# XBee-Explorer.net
KiCad netlist of a schematic drawn in EAGLE
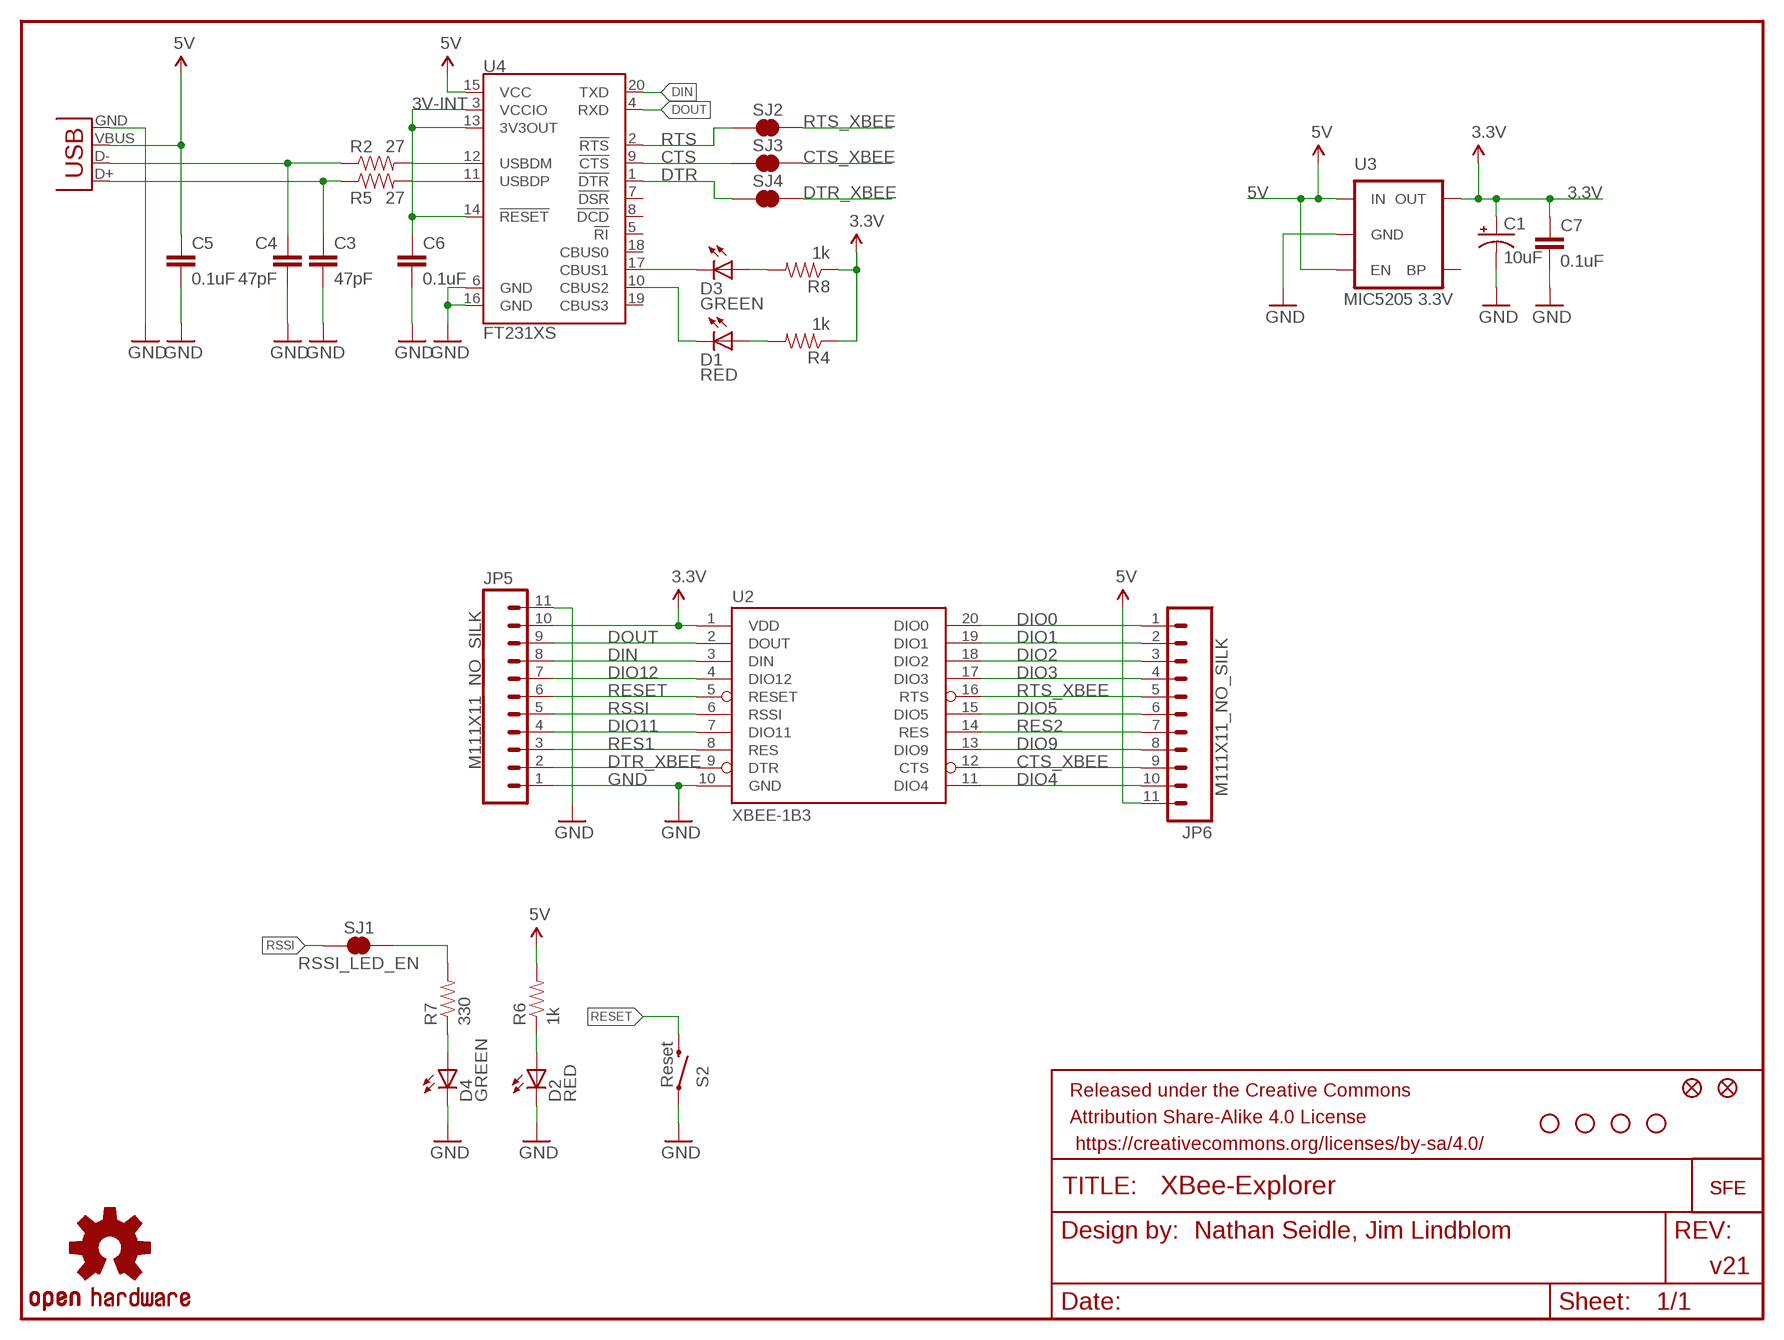
[diagram p0: schematic, sheet 1]

(export (version "E")
  (design (tool "Eeschema 10.0.6"))
  (components
    (comp (ref "C1")
      (value "10uF")
      (footprint "eagle-import:EIA3216")
      (libsource (lib "eagle-import") (part "CAP_POL1206"))
    )
    (comp (ref "C3")
      (value "47pF")
      (footprint "eagle-import:0603-CAP")
      (libsource (lib "eagle-import") (part "CAP0603-CAP"))
    )
    (comp (ref "C4")
      (value "47pF")
      (footprint "eagle-import:0603-CAP")
      (libsource (lib "eagle-import") (part "CAP0603-CAP"))
    )
    (comp (ref "C5")
      (value "0.1uF")
      (footprint "eagle-import:0603-CAP")
      (libsource (lib "eagle-import") (part "CAP0603-CAP"))
    )
    (comp (ref "C6")
      (value "0.1uF")
      (footprint "eagle-import:0603-CAP")
      (libsource (lib "eagle-import") (part "CAP0603-CAP"))
    )
    (comp (ref "C7")
      (value "0.1uF")
      (footprint "eagle-import:0603-CAP")
      (libsource (lib "eagle-import") (part "CAP0603-CAP"))
    )
    (comp (ref "D1")
      (value "RED")
      (footprint "eagle-import:LED-0603")
      (libsource (lib "eagle-import") (part "LED-RED0603"))
    )
    (comp (ref "D2")
      (value "RED")
      (footprint "eagle-import:LED-0603")
      (libsource (lib "eagle-import") (part "LED-RED0603"))
    )
    (comp (ref "D3")
      (value "GREEN")
      (footprint "eagle-import:LED-0603")
      (libsource (lib "eagle-import") (part "LED-GREEN0603"))
    )
    (comp (ref "D4")
      (value "GREEN")
      (footprint "eagle-import:LED-0603")
      (libsource (lib "eagle-import") (part "LED-GREEN0603"))
    )
    (comp (ref "FRAME1")
      (value "FRAME-LETTER")
      (footprint "eagle-import:CREATIVE_COMMONS")
      (libsource (lib "eagle-import") (part "FRAME-LETTER"))
    )
    (comp (ref "JP1")
      (value "FIDUCIAL1X2")
      (footprint "eagle-import:FIDUCIAL-1X2")
      (libsource (lib "eagle-import") (part "FIDUCIAL1X2"))
    )
    (comp (ref "JP4")
      (value "FIDUCIAL1X2")
      (footprint "eagle-import:FIDUCIAL-1X2")
      (libsource (lib "eagle-import") (part "FIDUCIAL1X2"))
    )
    (comp (ref "JP5")
      (value "M111X11_NO_SILK")
      (footprint "eagle-import:1X11_NO_SILK")
      (libsource (lib "eagle-import") (part "M111X11_NO_SILK"))
    )
    (comp (ref "JP6")
      (value "M111X11_NO_SILK")
      (footprint "eagle-import:1X11_NO_SILK")
      (libsource (lib "eagle-import") (part "M111X11_NO_SILK"))
    )
    (comp (ref "LOGO1")
      (value "OSHW-LOGOS")
      (footprint "eagle-import:OSHW-LOGO-S")
      (libsource (lib "eagle-import") (part "OSHW-LOGOS"))
    )
    (comp (ref "R2")
      (value "27")
      (footprint "eagle-import:0603-RES")
      (libsource (lib "eagle-import") (part "RESISTOR0603-RES"))
    )
    (comp (ref "R4")
      (value "1k")
      (footprint "eagle-import:0603-RES")
      (libsource (lib "eagle-import") (part "RESISTOR0603-RES"))
    )
    (comp (ref "R5")
      (value "27")
      (footprint "eagle-import:0603-RES")
      (libsource (lib "eagle-import") (part "RESISTOR0603-RES"))
    )
    (comp (ref "R6")
      (value "1k")
      (footprint "eagle-import:0603-RES")
      (libsource (lib "eagle-import") (part "RESISTOR0603-RES"))
    )
    (comp (ref "R7")
      (value "330")
      (footprint "eagle-import:0603-RES")
      (libsource (lib "eagle-import") (part "RESISTOR0603-RES"))
    )
    (comp (ref "R8")
      (value "1k")
      (footprint "eagle-import:0603-RES")
      (libsource (lib "eagle-import") (part "RESISTOR0603-RES"))
    )
    (comp (ref "S2")
      (value "Reset")
      (footprint "eagle-import:TACTILE_SWITCH_SMD")
      (libsource (lib "eagle-import") (part "SWITCH-MOMENTARY-2SMD"))
    )
    (comp (ref "SJ1")
      (value "RSSI_LED_EN")
      (footprint "eagle-import:SJ_2S-TRACE")
      (libsource (lib "eagle-import") (part "SOLDERJUMPERTRACE"))
    )
    (comp (ref "SJ2")
      (value "CTS_EN")
      (footprint "eagle-import:SJ_2S-TRACE")
      (libsource (lib "eagle-import") (part "SOLDERJUMPERTRACE"))
    )
    (comp (ref "SJ3")
      (value "RTS_EN")
      (footprint "eagle-import:SJ_2S-TRACE")
      (libsource (lib "eagle-import") (part "SOLDERJUMPERTRACE"))
    )
    (comp (ref "SJ4")
      (value "DTR")
      (footprint "eagle-import:SJ_2S-TRACE")
      (libsource (lib "eagle-import") (part "SOLDERJUMPERTRACE"))
    )
    (comp (ref "U$1")
      (value "LOGO-SFESK")
      (footprint "eagle-import:SFE-LOGO-FLAME")
      (libsource (lib "eagle-import") (part "LOGO-SFESK"))
    )
    (comp (ref "U$4")
      (value "LOGO-SFENEW")
      (footprint "eagle-import:SFE-NEW-WEBLOGO")
      (libsource (lib "eagle-import") (part "LOGO-SFENEW"))
    )
    (comp (ref "U$5")
      (value "STAND-OFF")
      (footprint "eagle-import:STAND-OFF")
      (libsource (lib "eagle-import") (part "STAND-OFF"))
    )
    (comp (ref "U$9")
      (value "STAND-OFF")
      (footprint "eagle-import:STAND-OFF")
      (libsource (lib "eagle-import") (part "STAND-OFF"))
    )
    (comp (ref "U$10")
      (value "STAND-OFF")
      (footprint "eagle-import:STAND-OFF")
      (libsource (lib "eagle-import") (part "STAND-OFF"))
    )
    (comp (ref "U$11")
      (value "STAND-OFF")
      (footprint "eagle-import:STAND-OFF")
      (libsource (lib "eagle-import") (part "STAND-OFF"))
    )
    (comp (ref "U2")
      (value "XBEE-1B3")
      (footprint "eagle-import:XBEE-SMD")
      (libsource (lib "eagle-import") (part "XBEE-1B3"))
    )
    (comp (ref "U3")
      (value "MIC5205 3.3V")
      (footprint "eagle-import:SOT23-5")
      (libsource (lib "eagle-import") (part "V_REG_LDOSMD"))
    )
    (comp (ref "U4")
      (value "FT231XS")
      (footprint "eagle-import:SSOP20_L")
      (libsource (lib "eagle-import") (part "FT231XS"))
    )
    (comp (ref "X1")
      (value "USBSMD")
      (footprint "eagle-import:USB-MINIB")
      (libsource (lib "eagle-import") (part "USBSMD"))
    )
  )
  (nets
    (net (code "1") (name "/3V-INT") (class "Default")
      (node (ref "C6") (pin "1") (pinfunction "1_1") (pintype "passive"))
      (node (ref "U4") (pin "13") (pinfunction "3V3OUT_13") (pintype "bidirectional"))
      (node (ref "U4") (pin "14") (pinfunction "~{RESET}_14") (pintype "bidirectional"))
      (node (ref "U4") (pin "3") (pinfunction "VCCIO_3") (pintype "bidirectional"))
    )
    (net (code "2") (name "/CTS") (class "Default")
      (node (ref "SJ3") (pin "1") (pinfunction "1_1") (pintype "passive"))
      (node (ref "U4") (pin "9") (pinfunction "~{CTS}_9") (pintype "bidirectional"))
    )
    (net (code "3") (name "/CTS_XBEE") (class "Default")
      (node (ref "JP6") (pin "9") (pinfunction "9_9") (pintype "passive"))
      (node (ref "SJ3") (pin "2") (pinfunction "2_2") (pintype "passive"))
      (node (ref "U2") (pin "12") (pinfunction "CTS_12") (pintype "output"))
    )
    (net (code "4") (name "/DIO0") (class "Default")
      (node (ref "JP6") (pin "1") (pinfunction "1_1") (pintype "passive"))
      (node (ref "U2") (pin "20") (pinfunction "DIO0_20") (pintype "bidirectional"))
    )
    (net (code "5") (name "/DIO1") (class "Default")
      (node (ref "JP6") (pin "2") (pinfunction "2_2") (pintype "passive"))
      (node (ref "U2") (pin "19") (pinfunction "DIO1_19") (pintype "bidirectional"))
    )
    (net (code "6") (name "/DIO2") (class "Default")
      (node (ref "JP6") (pin "3") (pinfunction "3_3") (pintype "passive"))
      (node (ref "U2") (pin "18") (pinfunction "DIO2_18") (pintype "bidirectional"))
    )
    (net (code "7") (name "/DIO3") (class "Default")
      (node (ref "JP6") (pin "4") (pinfunction "4_4") (pintype "passive"))
      (node (ref "U2") (pin "17") (pinfunction "DIO3_17") (pintype "bidirectional"))
    )
    (net (code "8") (name "/DIO4") (class "Default")
      (node (ref "JP6") (pin "10") (pinfunction "10_10") (pintype "passive"))
      (node (ref "U2") (pin "11") (pinfunction "DIO4_11") (pintype "bidirectional"))
    )
    (net (code "9") (name "/DIO5") (class "Default")
      (node (ref "JP6") (pin "6") (pinfunction "6_6") (pintype "passive"))
      (node (ref "U2") (pin "15") (pinfunction "DIO5_15") (pintype "bidirectional"))
    )
    (net (code "10") (name "/DIO9") (class "Default")
      (node (ref "JP6") (pin "8") (pinfunction "8_8") (pintype "passive"))
      (node (ref "U2") (pin "13") (pinfunction "DIO9_13") (pintype "bidirectional"))
    )
    (net (code "11") (name "/DIO11") (class "Default")
      (node (ref "JP5") (pin "4") (pinfunction "4_4") (pintype "passive"))
      (node (ref "U2") (pin "7") (pinfunction "DIO11_7") (pintype "bidirectional"))
    )
    (net (code "12") (name "/DIO12") (class "Default")
      (node (ref "JP5") (pin "7") (pinfunction "7_7") (pintype "passive"))
      (node (ref "U2") (pin "4") (pinfunction "DIO12_4") (pintype "bidirectional"))
    )
    (net (code "13") (name "/DTR") (class "Default")
      (node (ref "SJ4") (pin "1") (pinfunction "1_1") (pintype "passive"))
      (node (ref "U4") (pin "1") (pinfunction "~{DTR}_1") (pintype "bidirectional"))
    )
    (net (code "14") (name "/DTR_XBEE") (class "Default")
      (node (ref "JP5") (pin "2") (pinfunction "2_2") (pintype "passive"))
      (node (ref "SJ4") (pin "2") (pinfunction "2_2") (pintype "passive"))
      (node (ref "U2") (pin "9") (pinfunction "DTR_9") (pintype "bidirectional"))
    )
    (net (code "15") (name "/RES1") (class "Default")
      (node (ref "JP5") (pin "3") (pinfunction "3_3") (pintype "passive"))
      (node (ref "U2") (pin "8") (pinfunction "RES_8") (pintype "bidirectional"))
    )
    (net (code "16") (name "/RES2") (class "Default")
      (node (ref "JP6") (pin "7") (pinfunction "7_7") (pintype "passive"))
      (node (ref "U2") (pin "14") (pinfunction "RES_14") (pintype "bidirectional"))
    )
    (net (code "17") (name "/RTS") (class "Default")
      (node (ref "SJ2") (pin "1") (pinfunction "1_1") (pintype "passive"))
      (node (ref "U4") (pin "2") (pinfunction "~{RTS}_2") (pintype "bidirectional"))
    )
    (net (code "18") (name "/RTS_XBEE") (class "Default")
      (node (ref "JP6") (pin "5") (pinfunction "5_5") (pintype "passive"))
      (node (ref "SJ2") (pin "2") (pinfunction "2_2") (pintype "passive"))
      (node (ref "U2") (pin "16") (pinfunction "RTS_16") (pintype "input"))
    )
    (net (code "19") (name "3.3V") (class "Default")
      (node (ref "C1") (pin "A") (pinfunction "+_A") (pintype "passive"))
      (node (ref "C7") (pin "1") (pinfunction "1_1") (pintype "passive"))
      (node (ref "JP5") (pin "10") (pinfunction "10_10") (pintype "passive"))
      (node (ref "R4") (pin "1") (pinfunction "1_1") (pintype "passive"))
      (node (ref "R8") (pin "1") (pinfunction "1_1") (pintype "passive"))
      (node (ref "U2") (pin "1") (pinfunction "VDD_1") (pintype "power_in"))
      (node (ref "U3") (pin "5") (pinfunction "OUT_5") (pintype "passive"))
    )
    (net (code "20") (name "5V") (class "Default")
      (node (ref "C5") (pin "1") (pinfunction "1_1") (pintype "passive"))
      (node (ref "JP6") (pin "11") (pinfunction "11_11") (pintype "passive"))
      (node (ref "R6") (pin "2") (pinfunction "2_2") (pintype "passive"))
      (node (ref "U3") (pin "1") (pinfunction "IN_1") (pintype "input"))
      (node (ref "U3") (pin "3") (pinfunction "EN_3") (pintype "input"))
      (node (ref "U4") (pin "15") (pinfunction "VCC_15") (pintype "bidirectional"))
      (node (ref "X1") (pin "VBUS") (pinfunction "VBUS_VBUS") (pintype "bidirectional"))
    )
    (net (code "21") (name "DIN") (class "Default")
      (node (ref "JP5") (pin "8") (pinfunction "8_8") (pintype "passive"))
      (node (ref "U2") (pin "3") (pinfunction "DIN_3") (pintype "input"))
      (node (ref "U4") (pin "20") (pinfunction "TXD_20") (pintype "bidirectional"))
    )
    (net (code "22") (name "DOUT") (class "Default")
      (node (ref "JP5") (pin "9") (pinfunction "9_9") (pintype "passive"))
      (node (ref "U2") (pin "2") (pinfunction "DOUT_2") (pintype "output"))
      (node (ref "U4") (pin "4") (pinfunction "RXD_4") (pintype "bidirectional"))
    )
    (net (code "23") (name "GND") (class "Default")
      (node (ref "C1") (pin "C") (pinfunction "-_C") (pintype "passive"))
      (node (ref "C3") (pin "2") (pinfunction "2_2") (pintype "passive"))
      (node (ref "C4") (pin "2") (pinfunction "2_2") (pintype "passive"))
      (node (ref "C5") (pin "2") (pinfunction "2_2") (pintype "passive"))
      (node (ref "C6") (pin "2") (pinfunction "2_2") (pintype "passive"))
      (node (ref "C7") (pin "2") (pinfunction "2_2") (pintype "passive"))
      (node (ref "D2") (pin "C") (pinfunction "C_C") (pintype "passive"))
      (node (ref "D4") (pin "C") (pinfunction "C_C") (pintype "passive"))
      (node (ref "JP5") (pin "1") (pinfunction "1_1") (pintype "passive"))
      (node (ref "JP5") (pin "11") (pinfunction "11_11") (pintype "passive"))
      (node (ref "S2") (pin "1") (pinfunction "1_1") (pintype "passive"))
      (node (ref "U2") (pin "10") (pinfunction "GND_10") (pintype "power_in"))
      (node (ref "U3") (pin "2") (pinfunction "GND_2") (pintype "input"))
      (node (ref "U4") (pin "16") (pinfunction "GND_16") (pintype "bidirectional"))
      (node (ref "U4") (pin "6") (pinfunction "GND_6") (pintype "bidirectional"))
      (node (ref "X1") (pin "GND") (pinfunction "GND_GND") (pintype "bidirectional"))
    )
    (net (code "24") (name "Net-(C3-Pad1)") (class "Default")
      (node (ref "C3") (pin "1") (pinfunction "1_1") (pintype "passive"))
      (node (ref "R5") (pin "1") (pinfunction "1_1") (pintype "passive"))
      (node (ref "X1") (pin "D+") (pinfunction "D+_D+") (pintype "bidirectional"))
    )
    (net (code "25") (name "Net-(C4-Pad1)") (class "Default")
      (node (ref "C4") (pin "1") (pinfunction "1_1") (pintype "passive"))
      (node (ref "R2") (pin "1") (pinfunction "1_1") (pintype "passive"))
      (node (ref "X1") (pin "D-") (pinfunction "D-_D-") (pintype "bidirectional"))
    )
    (net (code "26") (name "Net-(D1-PadA)") (class "Default")
      (node (ref "D1") (pin "A") (pinfunction "A_A") (pintype "passive"))
      (node (ref "R4") (pin "2") (pinfunction "2_2") (pintype "passive"))
    )
    (net (code "27") (name "Net-(D2-PadA)") (class "Default")
      (node (ref "D2") (pin "A") (pinfunction "A_A") (pintype "passive"))
      (node (ref "R6") (pin "1") (pinfunction "1_1") (pintype "passive"))
    )
    (net (code "28") (name "Net-(D3-PadA)") (class "Default")
      (node (ref "D3") (pin "A") (pinfunction "A_A") (pintype "passive"))
      (node (ref "R8") (pin "2") (pinfunction "2_2") (pintype "passive"))
    )
    (net (code "29") (name "Net-(D4-PadA)") (class "Default")
      (node (ref "D4") (pin "A") (pinfunction "A_A") (pintype "passive"))
      (node (ref "R7") (pin "1") (pinfunction "1_1") (pintype "passive"))
    )
    (net (code "30") (name "Net-(R7-Pad2)") (class "Default")
      (node (ref "R7") (pin "2") (pinfunction "2_2") (pintype "passive"))
      (node (ref "SJ1") (pin "2") (pinfunction "2_2") (pintype "passive"))
    )
    (net (code "31") (name "Net-(U4-CBUS1)") (class "Default")
      (node (ref "D3") (pin "C") (pinfunction "C_C") (pintype "passive"))
      (node (ref "U4") (pin "17") (pinfunction "CBUS1_17") (pintype "bidirectional"))
    )
    (net (code "32") (name "Net-(U4-CBUS2)") (class "Default")
      (node (ref "D1") (pin "C") (pinfunction "C_C") (pintype "passive"))
      (node (ref "U4") (pin "10") (pinfunction "CBUS2_10") (pintype "bidirectional"))
    )
    (net (code "33") (name "Net-(U4-USBDM)") (class "Default")
      (node (ref "R2") (pin "2") (pinfunction "2_2") (pintype "passive"))
      (node (ref "U4") (pin "12") (pinfunction "USBDM_12") (pintype "bidirectional"))
    )
    (net (code "34") (name "Net-(U4-USBDP)") (class "Default")
      (node (ref "R5") (pin "2") (pinfunction "2_2") (pintype "passive"))
      (node (ref "U4") (pin "11") (pinfunction "USBDP_11") (pintype "bidirectional"))
    )
    (net (code "35") (name "RESET") (class "Default")
      (node (ref "JP5") (pin "6") (pinfunction "6_6") (pintype "passive"))
      (node (ref "S2") (pin "3") (pinfunction "2_3") (pintype "passive"))
      (node (ref "U2") (pin "5") (pinfunction "RESET_5") (pintype "input"))
    )
    (net (code "36") (name "RSSI") (class "Default")
      (node (ref "JP5") (pin "5") (pinfunction "5_5") (pintype "passive"))
      (node (ref "SJ1") (pin "1") (pinfunction "1_1") (pintype "passive"))
      (node (ref "U2") (pin "6") (pinfunction "RSSI_6") (pintype "bidirectional"))
    )
    (net (code "37") (name "unconnected-(U3-BP-Pad4)") (class "Default")
      (node (ref "U3") (pin "4") (pinfunction "BP_4") (pintype "input"))
    )
    (net (code "38") (name "unconnected-(U4-CBUS0-Pad18)") (class "Default")
      (node (ref "U4") (pin "18") (pinfunction "CBUS0_18") (pintype "bidirectional"))
    )
    (net (code "39") (name "unconnected-(U4-CBUS3-Pad19)") (class "Default")
      (node (ref "U4") (pin "19") (pinfunction "CBUS3_19") (pintype "bidirectional"))
    )
    (net (code "40") (name "unconnected-(U4-~{DCD}-Pad8)") (class "Default")
      (node (ref "U4") (pin "8") (pinfunction "~{DCD}_8") (pintype "bidirectional"))
    )
    (net (code "41") (name "unconnected-(U4-~{DSR}-Pad7)") (class "Default")
      (node (ref "U4") (pin "7") (pinfunction "~{DSR}_7") (pintype "bidirectional"))
    )
    (net (code "42") (name "unconnected-(U4-~{RI}-Pad5)") (class "Default")
      (node (ref "U4") (pin "5") (pinfunction "~{RI}_5") (pintype "bidirectional"))
    )
  )
)
